# Terra_Spray.net
KiCad netlist of a schematic drawn in Altium Designer
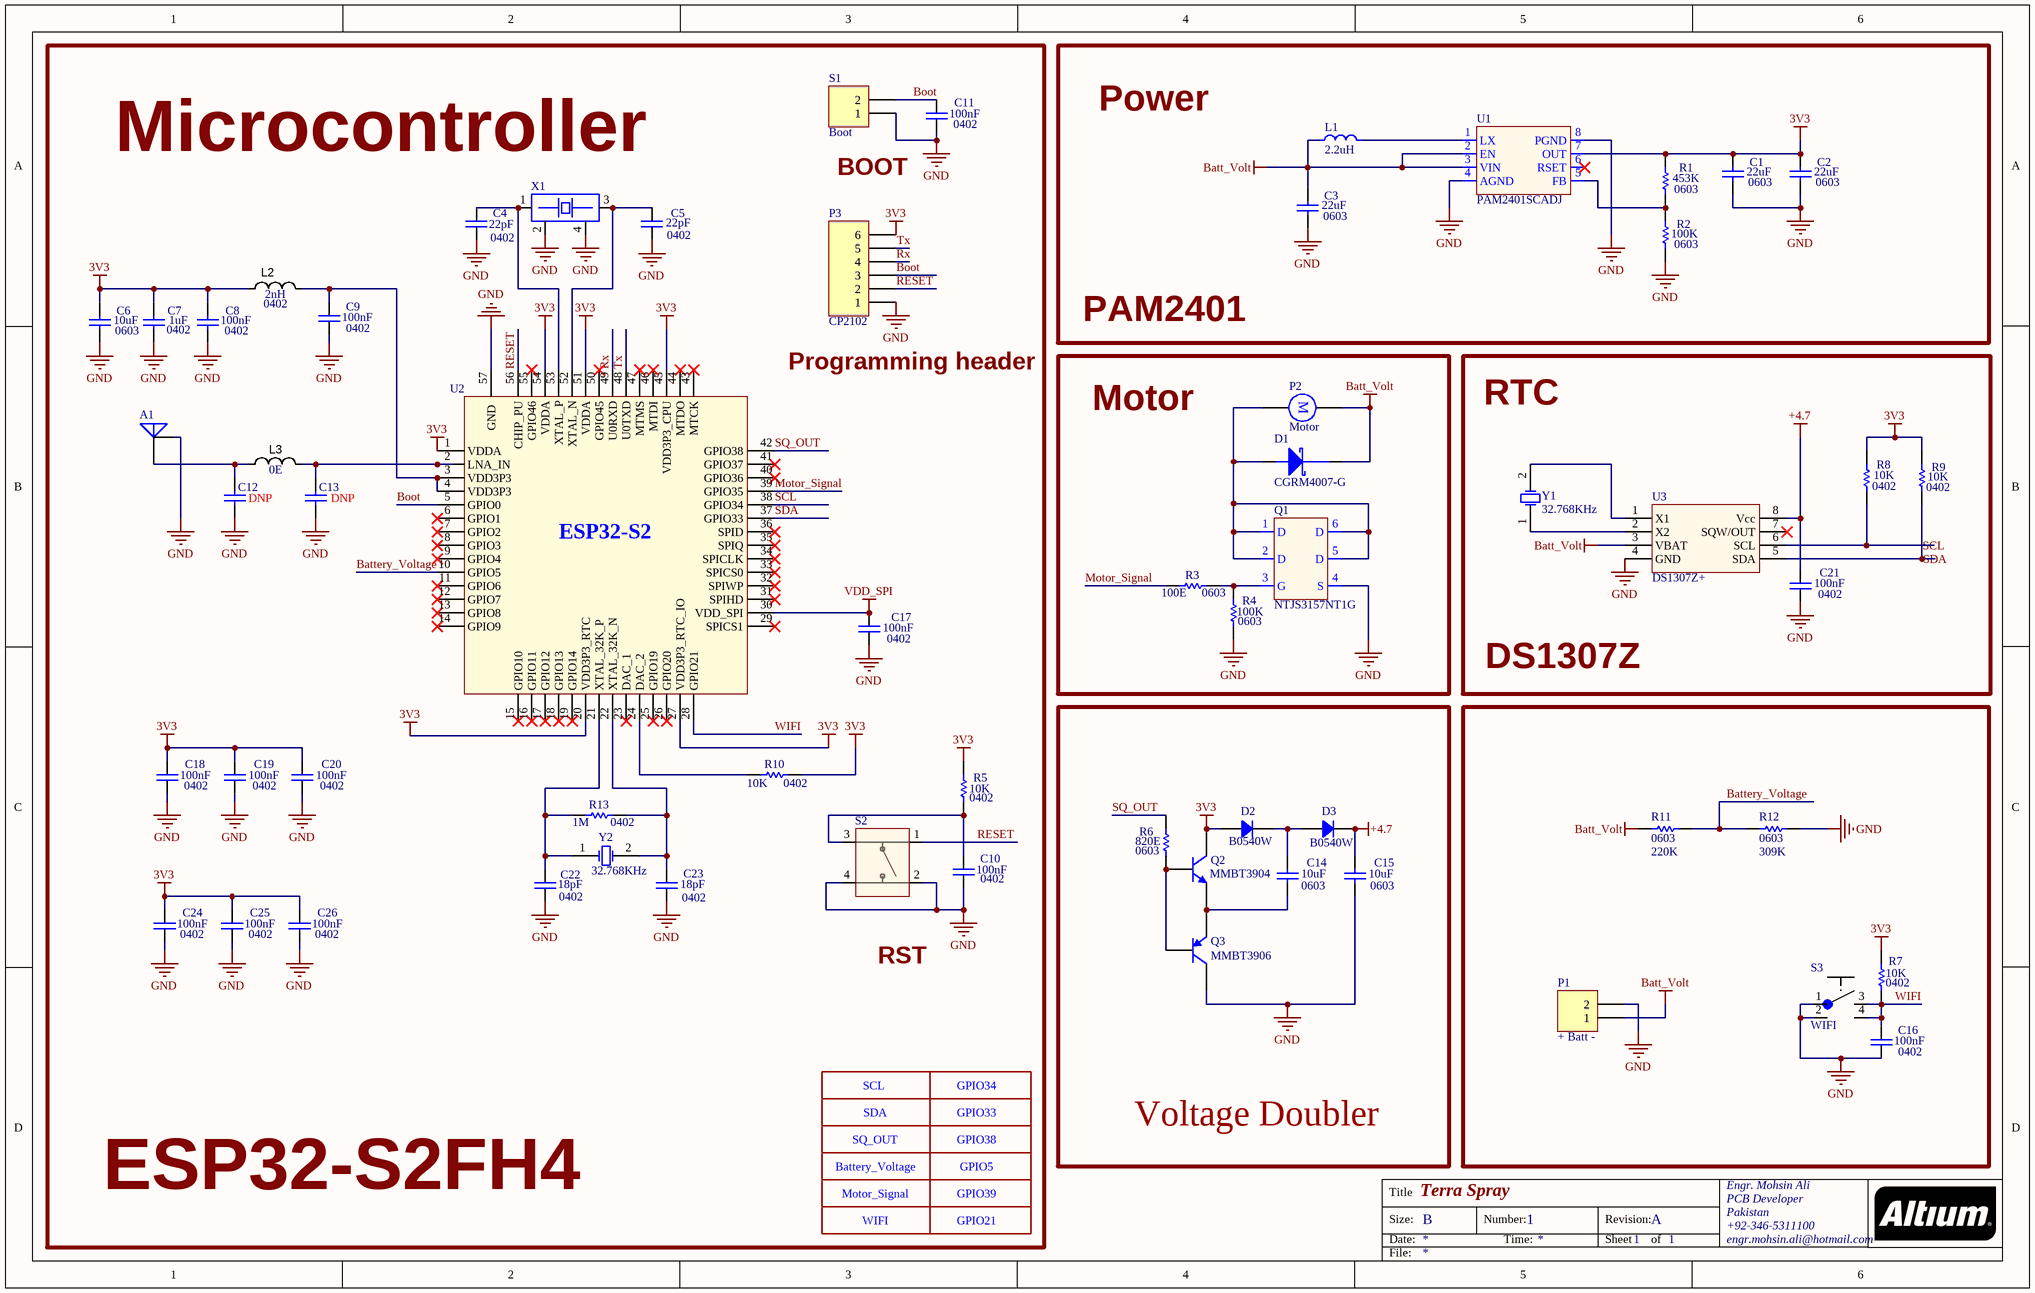
[diagram p0: Terra_Spray.SchDoc]

(export (version "E")
  (design (tool "Eeschema 10.0.6"))
  (components
    (comp (ref "A1")
      (value "Antenna_1")
      (footprint "ESP32 ANT")
      (description "PCB Antenna")
      (fields (field (name "PUBLISHER") "Altium Limited"))
      (libsource (lib "Pd's Sch Lib") (part "Antenna_1"))
    )
    (comp (ref "C1")
      (value "22uF")
      (footprint "CAPC0603")
      (description "Ceramic Capacitor,22uF,0603,6.3V")
      (fields (field (name "CASE/PACKAGE") "0603") (field (name "Comment") "Capacitor"))
      (libsource (lib "Pd's Sch Lib") (part "Capacitor"))
    )
    (comp (ref "C2")
      (value "22uF")
      (footprint "CAPC0603")
      (description "Ceramic Capacitor,22uF,0603,6.3V")
      (fields (field (name "CASE/PACKAGE") "0603") (field (name "Comment") "Capacitor"))
      (libsource (lib "Pd's Sch Lib") (part "Capacitor"))
    )
    (comp (ref "C3")
      (value "22uF")
      (footprint "CAPC0603")
      (description "Ceramic Capacitor,22uF,0603,6.3V")
      (fields (field (name "CASE/PACKAGE") "0603") (field (name "Comment") "Capacitor"))
      (libsource (lib "Pd's Sch Lib") (part "Capacitor"))
    )
    (comp (ref "C4")
      (value "22pF")
      (footprint "capc0402")
      (description "Ceramic Capacitor,22pF,0402,50V")
      (fields (field (name "CASE/PACKAGE") "0402") (field (name "Comment") "Cap"))
      (libsource (lib "CUSTOM TNY290PG") (part "Cap"))
    )
    (comp (ref "C5")
      (value "22pF")
      (footprint "capc0402")
      (description "Ceramic Capacitor,22pF,0402,50V")
      (fields (field (name "CASE/PACKAGE") "0402") (field (name "Comment") "Cap"))
      (libsource (lib "CUSTOM TNY290PG") (part "Cap"))
    )
    (comp (ref "C6")
      (value "10uF")
      (footprint "CAPC0603")
      (description "Ceramic Capacitor,10uF,0603,10V")
      (fields (field (name "CASE/PACKAGE") "0603") (field (name "Comment") "Capacitor"))
      (libsource (lib "Pd's Sch Lib") (part "Capacitor"))
    )
    (comp (ref "C7")
      (value "1uF")
      (footprint "CAPC0402")
      (description "Ceramic Capacitor,1uF,0402,6.3V")
      (fields (field (name "CASE/PACKAGE") "0402") (field (name "Comment") "Capacitor"))
      (libsource (lib "Pd's Sch Lib") (part "Capacitor"))
    )
    (comp (ref "C8")
      (value "100nF")
      (footprint "CAPC0402")
      (description "Ceramic Capacitor,100nF,0402,6.3V")
      (fields (field (name "CASE/PACKAGE") "0402") (field (name "Comment") "Cap"))
      (libsource (lib "Pd's Sch Lib") (part "Capacitor"))
    )
    (comp (ref "C9")
      (value "100nF")
      (footprint "CAPC0402")
      (description "Ceramic Capacitor,100nF,0402,6.3V")
      (fields (field (name "CASE/PACKAGE") "0402") (field (name "Comment") "Cap"))
      (libsource (lib "CUSTOM TNY290PG") (part "Cap"))
    )
    (comp (ref "C10")
      (value "100nF")
      (footprint "CAPC0402")
      (description "Ceramic Capacitor,100nF,0402,6.3V")
      (fields (field (name "CASE/PACKAGE") "0402") (field (name "Comment") "Cap"))
      (libsource (lib "CUSTOM TNY290PG") (part "Cap"))
    )
    (comp (ref "C11")
      (value "100nF")
      (footprint "CAPC0402")
      (description "Ceramic Capacitor,100nF,0402,6.3V")
      (fields (field (name "CASE/PACKAGE") "0402") (field (name "Comment") "Cap"))
      (libsource (lib "CUSTOM TNY290PG") (part "Cap"))
    )
    (comp (ref "C12")
      (value "Capacitor")
      (footprint "CAPC0402")
      (libsource (lib "Pd's Sch Lib") (part "Capacitor"))
    )
    (comp (ref "C13")
      (value "Capacitor")
      (footprint "CAPC0402")
      (libsource (lib "Pd's Sch Lib") (part "Capacitor"))
    )
    (comp (ref "C14")
      (value "10uF")
      (footprint "CAPC0603")
      (description "Ceramic Capacitor,10uF,0603,10V")
      (fields (field (name "CASE/PACKAGE") "0603") (field (name "Comment") "Capacitor"))
      (libsource (lib "") (part "Capacitor_1"))
    )
    (comp (ref "C15")
      (value "10uF")
      (footprint "CAPC0603")
      (description "Ceramic Capacitor,10uF,0603,10V")
      (fields (field (name "CASE/PACKAGE") "0603") (field (name "Comment") "Capacitor"))
      (libsource (lib "") (part "Capacitor_1"))
    )
    (comp (ref "C16")
      (value "100nF")
      (footprint "CAPC0402")
      (description "Ceramic Capacitor,100nF,0402,6.3V")
      (fields (field (name "CASE/PACKAGE") "0402") (field (name "Comment") "Cap"))
      (libsource (lib "CUSTOM TNY290PG") (part "Cap"))
    )
    (comp (ref "C17")
      (value "100nF")
      (footprint "CAPC0402")
      (description "Ceramic Capacitor,100nF,0402,6.3V")
      (fields (field (name "CASE/PACKAGE") "0402") (field (name "Comment") "Cap"))
      (libsource (lib "CUSTOM TNY290PG") (part "Cap"))
    )
    (comp (ref "C18")
      (value "100nF")
      (footprint "CAPC0402")
      (description "Ceramic Capacitor,100nF,0402,6.3V")
      (fields (field (name "CASE/PACKAGE") "0402") (field (name "Comment") "Cap"))
      (libsource (lib "CUSTOM TNY290PG") (part "Cap"))
    )
    (comp (ref "C19")
      (value "100nF")
      (footprint "CAPC0402")
      (description "Ceramic Capacitor,100nF,0402,6.3V")
      (fields (field (name "CASE/PACKAGE") "0402") (field (name "Comment") "Cap"))
      (libsource (lib "CUSTOM TNY290PG") (part "Cap"))
    )
    (comp (ref "C20")
      (value "100nF")
      (footprint "CAPC0402")
      (description "Ceramic Capacitor,100nF,0402,6.3V")
      (fields (field (name "CASE/PACKAGE") "0402") (field (name "Comment") "Cap"))
      (libsource (lib "CUSTOM TNY290PG") (part "Cap"))
    )
    (comp (ref "C21")
      (value "100nF")
      (footprint "CAPC0402")
      (description "Ceramic Capacitor,100nF,0402,6.3V")
      (fields (field (name "CASE/PACKAGE") "0402") (field (name "Comment") "Cap"))
      (libsource (lib "CUSTOM TNY290PG") (part "Cap"))
    )
    (comp (ref "C22")
      (value "18pF")
      (footprint "capc0402")
      (description "Ceramic Capacitor,18pF,0402,50V")
      (fields (field (name "CASE/PACKAGE") "0402") (field (name "Comment") "Cap"))
      (libsource (lib "CUSTOM TNY290PG") (part "Cap"))
    )
    (comp (ref "C23")
      (value "18pF")
      (footprint "capc0402")
      (description "Ceramic Capacitor,18pF,0402,50V")
      (fields (field (name "CASE/PACKAGE") "0402") (field (name "Comment") "Cap"))
      (libsource (lib "CUSTOM TNY290PG") (part "Cap"))
    )
    (comp (ref "C24")
      (value "100nF")
      (footprint "CAPC0402")
      (description "Ceramic Capacitor,100nF,0402,6.3V")
      (fields (field (name "CASE/PACKAGE") "0402") (field (name "Comment") "Cap"))
      (libsource (lib "CUSTOM TNY290PG") (part "Cap"))
    )
    (comp (ref "C25")
      (value "100nF")
      (footprint "CAPC0402")
      (description "Ceramic Capacitor,100nF,0402,6.3V")
      (fields (field (name "CASE/PACKAGE") "0402") (field (name "Comment") "Cap"))
      (libsource (lib "CUSTOM TNY290PG") (part "Cap"))
    )
    (comp (ref "C26")
      (value "100nF")
      (footprint "CAPC0402")
      (description "Ceramic Capacitor,100nF,0402,6.3V")
      (fields (field (name "CASE/PACKAGE") "0402") (field (name "Comment") "Cap"))
      (libsource (lib "CUSTOM TNY290PG") (part "Cap"))
    )
    (comp (ref "D1")
      (value "CGRM4007-G")
      (footprint "SOD-123")
      (description "CGRM4007-G; SMT Diode; 1000V 1A; 2-Pin SOD-123")
      (fields (field (name "MANUFACTURER") "Comchip") (field (name "VOLTAGE") "1kV"))
      (libsource (lib "Integrated_Library_FEDEVEL_APR_2015") (part "BAT54HT1G"))
    )
    (comp (ref "D2")
      (value "B0540W")
      (footprint "SOD123 - duplicate")
      (description "Diode Schottky 40V 0.5A 2-Pin SOD-123 T/R")
      (libsource (lib "Pd's Sch Lib") (part "Diode"))
    )
    (comp (ref "D3")
      (value "B0540W")
      (footprint "SOD123 - duplicate")
      (description "Diode Schottky 40V 0.5A 2-Pin SOD-123 T/R")
      (libsource (lib "Pd's Sch Lib") (part "Diode"))
    )
    (comp (ref "L1")
      (value "2.2uH")
      (footprint "INDP5050X20N")
      (description "SMD Power Inductors ROHS")
      (fields (field (name "MANUFACTURER PART NUMBER") "FNR5012S2R2MT") (field (name "Comment") "Inductor"))
      (libsource (lib "Inductors") (part "74404052022"))
    )
    (comp (ref "L2")
      (value "Inductor")
      (footprint "inductor 0402")
      (description "2nH ±0.3nH 900mA 120mΩ 0402 Inductors (SMD) RoHS")
      (fields
        (field (name "MANUFACTURER PART NUMBER") "LQG15HN2N0S02D")
        (field (name "CASE/PACKAGE") "0402")
        (field (name "INDUCTANCE") "2nH")
      )
      (libsource (lib "Pd's Sch Lib") (part "Inductor"))
    )
    (comp (ref "L3")
      (value "0E")
      (footprint "inductor 0402")
      (description "Thick Film Resistor -  0ohm, 1%, 0402")
      (fields (field (name "Comment") "Inductor"))
      (libsource (lib "Pd's Sch Lib") (part "Inductor"))
    )
    (comp (ref "P1")
      (value "+ Batt -")
      (footprint "2 pin 2.5mm - Header")
      (description "Header, 2-Pin")
      (fields (field (name "PUBLISHER") "Altium Limited"))
      (libsource (lib "Miscellaneous Connectors") (part "Header 2"))
    )
    (comp (ref "P2")
      (value "Motor")
      (footprint "2 pin 2.5mm - Header")
      (description "Motor, General Kind")
      (fields (field (name "PUBLISHER") "Altium Limited"))
      (libsource (lib "Miscellaneous Devices") (part "Motor"))
    )
    (comp (ref "P3")
      (value "CP2102")
      (footprint "Header 6x1")
      (description "Header, 6-Pin")
      (fields (field (name "PUBLISHER") "Altium Limited"))
      (libsource (lib "Miscellaneous Connectors") (part "Header 6"))
    )
    (comp (ref "Q1")
      (value "Mosfet")
      (footprint "SOT-363")
      (description "Trans MOSFET N-CH 20V 3.2A 6-Pin SC-88 T/R")
      (fields (field (name "MANUFACTURER PART NUMBER") "NTJS3157NT1G"))
      (libsource (lib "Terra_Spray") (part "NTJS3157NT1G"))
    )
    (comp (ref "Q2")
      (value "NPN BJT Transistor")
      (footprint "SOT-23")
      (description "Bipolar Transistors - BJT SOT-23 NPN")
      (fields (field (name "MANUFACTURER PART NUMBER") "MMBT3904"))
      (libsource (lib "Pd's Sch Lib") (part "NPN BJT Transistor"))
    )
    (comp (ref "Q3")
      (value "PNP BJT Transistor")
      (footprint "SOT-23")
      (fields
        (field (name "MANUFACTURER") "ON Semiconductor")
        (field (name "MANUFACTURER PART NUMBER") "MMBT3906")
      )
      (libsource (lib "Pd's Sch Lib") (part "PNP BJT Transistor"))
    )
    (comp (ref "R1")
      (value "453K")
      (footprint "RESC0603")
      (description "Thick Film Resistor -  453Kohm, 1%, 0603")
      (fields (field (name "CASE/PACKAGE") "0603") (field (name "Comment") "Resistor"))
      (libsource (lib "Pd's Sch Lib") (part "Resistor"))
    )
    (comp (ref "R2")
      (value "100K")
      (footprint "RESC0603")
      (description "Thick Film Resistor -  100Kohm, 1%, 0603")
      (fields (field (name "CASE/PACKAGE") "0603") (field (name "Comment") "Resistor"))
      (libsource (lib "Pd's Sch Lib") (part "Resistor"))
    )
    (comp (ref "R3")
      (value "100E")
      (footprint "RESC0603")
      (description "Thick Film Resistor -  100ohm, 1%, 0603")
      (fields (field (name "CASE/PACKAGE") "0603") (field (name "Comment") "Resistor"))
      (libsource (lib "Pd's Sch Lib") (part "Resistor"))
    )
    (comp (ref "R4")
      (value "100K")
      (footprint "RESC0603")
      (description "Thick Film Resistor -  100Kohm, 1%, 0603")
      (fields (field (name "CASE/PACKAGE") "0603") (field (name "Comment") "Resistor"))
      (libsource (lib "Pd's Sch Lib") (part "Resistor"))
    )
    (comp (ref "R5")
      (value "10K")
      (footprint "RESC0402")
      (description "Thick Film Resistor -  10Kohm, 1%, 0402")
      (fields (field (name "CASE/PACKAGE") "0402") (field (name "Comment") "Resistor"))
      (libsource (lib "Pd's Sch Lib") (part "Resistor"))
    )
    (comp (ref "R6")
      (value "820E")
      (footprint "RESC0603")
      (description "Thick Film Resistor -  820ohm, 1%, 0603")
      (fields (field (name "CASE/PACKAGE") "0603") (field (name "Comment") "Resistor"))
      (libsource (lib "Pd's Sch Lib") (part "Resistor"))
    )
    (comp (ref "R7")
      (value "10K")
      (footprint "RESC0402")
      (description "Thick Film Resistor -  10Kohm, 1%, 0402")
      (fields (field (name "CASE/PACKAGE") "0402") (field (name "Comment") "Resistor"))
      (libsource (lib "Pd's Sch Lib") (part "Resistor"))
    )
    (comp (ref "R8")
      (value "10K")
      (footprint "RESC0402")
      (description "Thick Film Resistor -  10Kohm, 1%, 0402")
      (fields (field (name "CASE/PACKAGE") "0402") (field (name "Comment") "Resistor"))
      (libsource (lib "Pd's Sch Lib") (part "Resistor"))
    )
    (comp (ref "R9")
      (value "10K")
      (footprint "RESC0402")
      (description "Thick Film Resistor -  10Kohm, 1%, 0402")
      (fields (field (name "CASE/PACKAGE") "0402") (field (name "Comment") "Resistor"))
      (libsource (lib "Pd's Sch Lib") (part "Resistor"))
    )
    (comp (ref "R10")
      (value "10K")
      (footprint "RESC0402")
      (description "Thick Film Resistor -  10Kohm, 1%, 0402")
      (fields (field (name "CASE/PACKAGE") "0402") (field (name "Comment") "Resistor"))
      (libsource (lib "Pd's Sch Lib") (part "Resistor"))
    )
    (comp (ref "R11")
      (value "220K")
      (footprint "RESC0603")
      (description "Thick Film Resistor -  220Kohm, 1%, 0603")
      (fields (field (name "CASE/PACKAGE") "0603") (field (name "Comment") "Resistor"))
      (libsource (lib "Pd's Sch Lib") (part "Resistor"))
    )
    (comp (ref "R12")
      (value "309K")
      (footprint "RESC0603")
      (description "Thick Film Resistor -  309Kohm, 1%, 0603")
      (fields (field (name "CASE/PACKAGE") "0603") (field (name "Comment") "Resistor"))
      (libsource (lib "Pd's Sch Lib") (part "Resistor"))
    )
    (comp (ref "R13")
      (value "1M")
      (footprint "RESC0402")
      (description "Thick Film Resistor -  1Mohm, 1%, 0402")
      (fields (field (name "CASE/PACKAGE") "0402") (field (name "Comment") "Resistor"))
      (libsource (lib "Pd's Sch Lib") (part "Resistor"))
    )
    (comp (ref "S1")
      (value "Boot")
      (footprint "Switch Replacement")
      (description "Header, 2-Pin")
      (fields (field (name "PUBLISHER") "Altium Limited"))
      (libsource (lib "Miscellaneous Connectors") (part "Header 2"))
    )
    (comp (ref "S2")
      (value "Button")
      (footprint "434153017835")
      (description "3mm Square Plunger 50mA Top触动 3.5mm SPST 12V SMD Tactile Switches ROHS")
      (fields (field (name "MANUFACTURER PART NUMBER") "TS-1809SM-C"))
      (libsource (lib "Buttons") (part "434153017835"))
    )
    (comp (ref "S3")
      (value "WIFI")
      (footprint "FSMJ - SMD - Wifi")
      (description "Pushbutton 6x6mm, Actuator Height off PCB, Vertical 9.50mm")
      (fields (field (name "MF") "TE Connectivity") (field (name "MP") "FSM14J"))
      (libsource (lib "Main_PCB") (part "FSM14J"))
    )
    (comp (ref "U1")
      (value "PAM2401SCADJ")
      (footprint "8-TSSOP, 8-MSOP")
      (description "IC REG BOOST ADJ 3A SYNC 8MSOP")
      (libsource (lib "Regulators") (part "PAM2401SCADJ"))
    )
    (comp (ref "U2")
      (value "ESP32-S2")
      (footprint "QFN56-7x7mm")
      (description "WiFi 802.11b/g/n Transceiver Module 2.4GHz")
      (fields (field (name "MANUFACTURER PART NUMBER") "ESP32-S2FH4"))
      (libsource (lib "Pd's Sch Lib") (part "ESP32-S2"))
    )
    (comp (ref "U3")
      (value "DS1307Z+")
      (footprint "SOIC-8")
      (description "SERIAL TIME CHIP 8PIN, SOIC")
      (fields (field (name "VOLTAGE") "5V"))
      (libsource (lib "IC's") (part "DS1307Z+"))
    )
    (comp (ref "X1")
      (value "CRYSTAL_1")
      (footprint "Crystal_3225")
      (description "40MHz ±10ppm 10pF 30Ω SMD-3225 SMD Crystal Resonators RoHS")
      (fields (field (name "MANUFACTURER PART NUMBER") "7M40000049"))
      (libsource (lib "Pd's Sch Lib") (part "CRYSTAL_1_1"))
    )
    (comp (ref "Y1")
      (value "32.768KHz")
      (footprint "32.728Khz")
      (description "Crystal Oscillator")
      (fields (field (name "PUBLISHER") "Altium Limited"))
      (libsource (lib "Miscellaneous Devices") (part "XTAL"))
    )
    (comp (ref "Y2")
      (value "32.768KHz")
      (footprint "32.728Khz")
      (description "Crystal Oscillator")
      (fields (field (name "PUBLISHER") "Altium Limited"))
      (libsource (lib "Miscellaneous Devices") (part "XTAL"))
    )
  )
  (nets
    (net (code "1") (name "+4.7") (class "Default")
      (node (ref "C15") (pin "1") (pinfunction "1_1") (pintype "passive"))
      (node (ref "C21") (pin "1") (pinfunction "1_1") (pintype "passive"))
      (node (ref "D3") (pin "K") (pinfunction "K_K") (pintype "passive"))
      (node (ref "U3") (pin "8") (pinfunction "Vcc_8") (pintype "passive"))
    )
    (net (code "2") (name "/Battery_Voltage") (class "Default")
      (node (ref "R11") (pin "1") (pinfunction "1_1") (pintype "passive"))
      (node (ref "R12") (pin "2") (pinfunction "2_2") (pintype "passive"))
      (node (ref "U2") (pin "10") (pinfunction "GPIO5_10") (pintype "passive"))
    )
    (net (code "3") (name "/Boot") (class "Default")
      (node (ref "C11") (pin "2") (pinfunction "2_2") (pintype "passive"))
      (node (ref "P3") (pin "3") (pinfunction "3_3") (pintype "passive"))
      (node (ref "S1") (pin "2") (pinfunction "2_2") (pintype "passive"))
      (node (ref "U2") (pin "5") (pinfunction "GPIO0_5") (pintype "passive"))
    )
    (net (code "10") (name "/Motor_Signal") (class "Default")
      (node (ref "R3") (pin "2") (pinfunction "2_2") (pintype "passive"))
      (node (ref "U2") (pin "39") (pinfunction "GPIO35_39") (pintype "passive"))
    )
    (net (code "11") (name "/RESET") (class "Default")
      (node (ref "P3") (pin "2") (pinfunction "2_2") (pintype "passive"))
      (node (ref "S2") (pin "1") (pinfunction "1_1") (pintype "passive"))
      (node (ref "U2") (pin "56") (pinfunction "CHIP_PU_56") (pintype "passive"))
    )
    (net (code "12") (name "/Rx") (class "Default")
      (node (ref "P3") (pin "4") (pinfunction "4_4") (pintype "passive"))
      (node (ref "U2") (pin "49") (pinfunction "U0RXD_49") (pintype "passive"))
    )
    (net (code "13") (name "/SCL") (class "Default")
      (node (ref "R8") (pin "1") (pinfunction "1_1") (pintype "passive"))
      (node (ref "U2") (pin "38") (pinfunction "GPIO34_38") (pintype "passive"))
      (node (ref "U3") (pin "6") (pinfunction "SCL_6") (pintype "passive"))
    )
    (net (code "14") (name "/SDA") (class "Default")
      (node (ref "R9") (pin "1") (pinfunction "1_1") (pintype "passive"))
      (node (ref "U2") (pin "37") (pinfunction "GPIO33_37") (pintype "passive"))
      (node (ref "U3") (pin "5") (pinfunction "SDA_5") (pintype "passive"))
    )
    (net (code "15") (name "/SQ_OUT") (class "Default")
      (node (ref "R6") (pin "2") (pinfunction "2_2") (pintype "passive"))
      (node (ref "U2") (pin "42") (pinfunction "GPIO38_42") (pintype "passive"))
    )
    (net (code "16") (name "/Tx") (class "Default")
      (node (ref "P3") (pin "5") (pinfunction "5_5") (pintype "passive"))
      (node (ref "U2") (pin "48") (pinfunction "U0TXD_48") (pintype "passive"))
    )
    (net (code "17") (name "/WIFI") (class "Default")
      (node (ref "C16") (pin "2") (pinfunction "2_2") (pintype "passive"))
      (node (ref "R7") (pin "1") (pinfunction "1_1") (pintype "passive"))
      (node (ref "S3") (pin "3") (pinfunction "2_3") (pintype "passive"))
      (node (ref "S3") (pin "4") (pinfunction "2_4") (pintype "passive"))
      (node (ref "U2") (pin "28") (pinfunction "GPIO21_28") (pintype "passive"))
    )
    (net (code "18") (name "3V3") (class "Default")
      (node (ref "C1") (pin "2") (pinfunction "2_2") (pintype "passive"))
      (node (ref "C18") (pin "1") (pinfunction "1_1") (pintype "passive"))
      (node (ref "C19") (pin "1") (pinfunction "1_1") (pintype "passive"))
      (node (ref "C2") (pin "2") (pinfunction "2_2") (pintype "passive"))
      (node (ref "C20") (pin "1") (pinfunction "1_1") (pintype "passive"))
      (node (ref "C24") (pin "1") (pinfunction "1_1") (pintype "passive"))
      (node (ref "C25") (pin "1") (pinfunction "1_1") (pintype "passive"))
      (node (ref "C26") (pin "1") (pinfunction "1_1") (pintype "passive"))
      (node (ref "C6") (pin "2") (pinfunction "2_2") (pintype "passive"))
      (node (ref "C7") (pin "2") (pinfunction "2_2") (pintype "passive"))
      (node (ref "C8") (pin "2") (pinfunction "2_2") (pintype "passive"))
      (node (ref "D2") (pin "A") (pinfunction "A_A") (pintype "passive"))
      (node (ref "L2") (pin "1") (pinfunction "1_1") (pintype "passive"))
      (node (ref "P3") (pin "6") (pinfunction "6_6") (pintype "passive"))
      (node (ref "Q2") (pin "3") (pinfunction "C_3") (pintype "passive"))
      (node (ref "R1") (pin "2") (pinfunction "2_2") (pintype "passive"))
      (node (ref "R10") (pin "1") (pinfunction "1_1") (pintype "passive"))
      (node (ref "R5") (pin "2") (pinfunction "2_2") (pintype "passive"))
      (node (ref "R7") (pin "2") (pinfunction "2_2") (pintype "passive"))
      (node (ref "R8") (pin "2") (pinfunction "2_2") (pintype "passive"))
      (node (ref "R9") (pin "2") (pinfunction "2_2") (pintype "passive"))
      (node (ref "U1") (pin "7") (pinfunction "OUT_7") (pintype "passive"))
      (node (ref "U2") (pin "1") (pinfunction "VDDA_1") (pintype "passive"))
      (node (ref "U2") (pin "20") (pinfunction "VDD3P3_RTC_20") (pintype "passive"))
      (node (ref "U2") (pin "27") (pinfunction "VDD3P3_RTC_IO_27") (pintype "passive"))
      (node (ref "U2") (pin "45") (pinfunction "VDD3P3_CPU_45") (pintype "passive"))
      (node (ref "U2") (pin "51") (pinfunction "VDDA_51") (pintype "passive"))
      (node (ref "U2") (pin "54") (pinfunction "VDDA_54") (pintype "passive"))
    )
    (net (code "19") (name "Batt_Volt") (class "Default")
      (node (ref "C3") (pin "2") (pinfunction "2_2") (pintype "passive"))
      (node (ref "D1") (pin "1") (pinfunction "Cathode_1") (pintype "passive"))
      (node (ref "L1") (pin "1") (pinfunction "1_1") (pintype "passive"))
      (node (ref "P1") (pin "1") (pinfunction "1_1") (pintype "passive"))
      (node (ref "P2") (pin "1") (pinfunction "1_1") (pintype "passive"))
      (node (ref "R11") (pin "2") (pinfunction "2_2") (pintype "passive"))
      (node (ref "U1") (pin "2") (pinfunction "EN_2") (pintype "passive"))
      (node (ref "U1") (pin "3") (pinfunction "VIN_3") (pintype "passive"))
      (node (ref "U3") (pin "3") (pinfunction "VBAT_3") (pintype "passive"))
    )
    (net (code "20") (name "GND") (class "Default")
      (node (ref "A1") (pin "2") (pinfunction "GND_2") (pintype "passive"))
      (node (ref "C1") (pin "1") (pinfunction "1_1") (pintype "passive"))
      (node (ref "C10") (pin "2") (pinfunction "2_2") (pintype "passive"))
      (node (ref "C11") (pin "1") (pinfunction "1_1") (pintype "passive"))
      (node (ref "C12") (pin "1") (pinfunction "1_1") (pintype "passive"))
      (node (ref "C13") (pin "1") (pinfunction "1_1") (pintype "passive"))
      (node (ref "C15") (pin "2") (pinfunction "2_2") (pintype "passive"))
      (node (ref "C16") (pin "1") (pinfunction "1_1") (pintype "passive"))
      (node (ref "C17") (pin "2") (pinfunction "2_2") (pintype "passive"))
      (node (ref "C18") (pin "2") (pinfunction "2_2") (pintype "passive"))
      (node (ref "C19") (pin "2") (pinfunction "2_2") (pintype "passive"))
      (node (ref "C2") (pin "1") (pinfunction "1_1") (pintype "passive"))
      (node (ref "C20") (pin "2") (pinfunction "2_2") (pintype "passive"))
      (node (ref "C21") (pin "2") (pinfunction "2_2") (pintype "passive"))
      (node (ref "C22") (pin "1") (pinfunction "1_1") (pintype "passive"))
      (node (ref "C23") (pin "1") (pinfunction "1_1") (pintype "passive"))
      (node (ref "C24") (pin "2") (pinfunction "2_2") (pintype "passive"))
      (node (ref "C25") (pin "2") (pinfunction "2_2") (pintype "passive"))
      (node (ref "C26") (pin "2") (pinfunction "2_2") (pintype "passive"))
      (node (ref "C3") (pin "1") (pinfunction "1_1") (pintype "passive"))
      (node (ref "C4") (pin "1") (pinfunction "1_1") (pintype "passive"))
      (node (ref "C5") (pin "1") (pinfunction "1_1") (pintype "passive"))
      (node (ref "C6") (pin "1") (pinfunction "1_1") (pintype "passive"))
      (node (ref "C7") (pin "1") (pinfunction "1_1") (pintype "passive"))
      (node (ref "C8") (pin "1") (pinfunction "1_1") (pintype "passive"))
      (node (ref "C9") (pin "2") (pinfunction "2_2") (pintype "passive"))
      (node (ref "P1") (pin "2") (pinfunction "2_2") (pintype "passive"))
      (node (ref "P3") (pin "1") (pinfunction "1_1") (pintype "passive"))
      (node (ref "Q1") (pin "4") (pinfunction "S_4") (pintype "passive"))
      (node (ref "Q3") (pin "3") (pinfunction "C_3") (pintype "passive"))
      (node (ref "R12") (pin "1") (pinfunction "1_1") (pintype "passive"))
      (node (ref "R2") (pin "2") (pinfunction "2_2") (pintype "passive"))
      (node (ref "R4") (pin "2") (pinfunction "2_2") (pintype "passive"))
      (node (ref "S1") (pin "1") (pinfunction "1_1") (pintype "passive"))
      (node (ref "S2") (pin "2") (pinfunction "2_2") (pintype "passive"))
      (node (ref "S2") (pin "4") (pinfunction "4_4") (pintype "passive"))
      (node (ref "S3") (pin "1") (pinfunction "1_1") (pintype "passive"))
      (node (ref "S3") (pin "2") (pinfunction "1_2") (pintype "passive"))
      (node (ref "U1") (pin "4") (pinfunction "AGND_4") (pintype "passive"))
      (node (ref "U1") (pin "8") (pinfunction "PGND_8") (pintype "passive"))
      (node (ref "U2") (pin "57") (pinfunction "GND_57") (pintype "passive"))
      (node (ref "U3") (pin "4") (pinfunction "GND_4") (pintype "passive"))
      (node (ref "X1") (pin "2") (pinfunction "2_2") (pintype "passive"))
      (node (ref "X1") (pin "4") (pinfunction "4_4") (pintype "passive"))
    )
    (net (code "21") (name "Net-(A1-ANT)") (class "Default")
      (node (ref "A1") (pin "1") (pinfunction "ANT_1") (pintype "passive"))
      (node (ref "C12") (pin "2") (pinfunction "2_2") (pintype "passive"))
      (node (ref "L3") (pin "1") (pinfunction "1_1") (pintype "passive"))
    )
    (net (code "22") (name "Net-(C9-Pad1)") (class "Default")
      (node (ref "C9") (pin "1") (pinfunction "1_1") (pintype "passive"))
      (node (ref "L2") (pin "2") (pinfunction "2_2") (pintype "passive"))
      (node (ref "U2") (pin "3") (pinfunction "VDD3P3_3") (pintype "passive"))
      (node (ref "U2") (pin "4") (pinfunction "VDD3P3_4") (pintype "passive"))
    )
    (net (code "23") (name "Net-(C10-Pad1)") (class "Default")
      (node (ref "C10") (pin "1") (pinfunction "1_1") (pintype "passive"))
      (node (ref "R5") (pin "1") (pinfunction "1_1") (pintype "passive"))
      (node (ref "S2") (pin "3") (pinfunction "3_3") (pintype "passive"))
    )
    (net (code "24") (name "Net-(C14-Pad1)") (class "Default")
      (node (ref "C14") (pin "1") (pinfunction "1_1") (pintype "passive"))
      (node (ref "D2") (pin "K") (pinfunction "K_K") (pintype "passive"))
      (node (ref "D3") (pin "A") (pinfunction "A_A") (pintype "passive"))
    )
    (net (code "25") (name "Net-(D1-Anode)") (class "Default")
      (node (ref "D1") (pin "2") (pinfunction "Anode_2") (pintype "passive"))
      (node (ref "P2") (pin "2") (pinfunction "2_2") (pintype "passive"))
      (node (ref "Q1") (pin "1") (pinfunction "D_1") (pintype "passive"))
      (node (ref "Q1") (pin "2") (pinfunction "D_2") (pintype "passive"))
      (node (ref "Q1") (pin "5") (pinfunction "D_5") (pintype "passive"))
      (node (ref "Q1") (pin "6") (pinfunction "D_6") (pintype "passive"))
    )
    (net (code "26") (name "Net-(Q1-G)") (class "Default")
      (node (ref "Q1") (pin "3") (pinfunction "G_3") (pintype "passive"))
      (node (ref "R3") (pin "1") (pinfunction "1_1") (pintype "passive"))
      (node (ref "R4") (pin "1") (pinfunction "1_1") (pintype "passive"))
    )
    (net (code "27") (name "Net-(Q2-B)") (class "Default")
      (node (ref "Q2") (pin "1") (pinfunction "B_1") (pintype "passive"))
      (node (ref "Q3") (pin "1") (pinfunction "B_1") (pintype "passive"))
      (node (ref "R6") (pin "1") (pinfunction "1_1") (pintype "passive"))
    )
    (net (code "28") (name "Net-(Q2-E)") (class "Default")
      (node (ref "C14") (pin "2") (pinfunction "2_2") (pintype "passive"))
      (node (ref "Q2") (pin "2") (pinfunction "E_2") (pintype "passive"))
      (node (ref "Q3") (pin "2") (pinfunction "E_2") (pintype "passive"))
    )
    (net (code "29") (name "Net-(U1-FB)") (class "Default")
      (node (ref "R1") (pin "1") (pinfunction "1_1") (pintype "passive"))
      (node (ref "R2") (pin "1") (pinfunction "1_1") (pintype "passive"))
      (node (ref "U1") (pin "5") (pinfunction "FB_5") (pintype "passive"))
    )
    (net (code "30") (name "Net-(U1-LX)") (class "Default")
      (node (ref "L1") (pin "2") (pinfunction "2_2") (pintype "passive"))
      (node (ref "U1") (pin "1") (pinfunction "LX_1") (pintype "passive"))
    )
    (net (code "31") (name "Net-(U2-DAC_2)") (class "Default")
      (node (ref "R10") (pin "2") (pinfunction "2_2") (pintype "passive"))
      (node (ref "U2") (pin "24") (pinfunction "DAC_2_24") (pintype "passive"))
    )
    (net (code "32") (name "Net-(U2-LNA_IN)") (class "Default")
      (node (ref "C13") (pin "2") (pinfunction "2_2") (pintype "passive"))
      (node (ref "L3") (pin "2") (pinfunction "2_2") (pintype "passive"))
      (node (ref "U2") (pin "2") (pinfunction "LNA_IN_2") (pintype "passive"))
    )
    (net (code "33") (name "Net-(U2-XTAL_32K_N)") (class "Default")
      (node (ref "C23") (pin "2") (pinfunction "2_2") (pintype "passive"))
      (node (ref "R13") (pin "2") (pinfunction "2_2") (pintype "passive"))
      (node (ref "U2") (pin "22") (pinfunction "XTAL_32K_N_22") (pintype "passive"))
      (node (ref "Y2") (pin "2") (pinfunction "OSC2_2") (pintype "passive"))
    )
    (net (code "34") (name "Net-(U2-XTAL_32K_P)") (class "Default")
      (node (ref "C22") (pin "2") (pinfunction "2_2") (pintype "passive"))
      (node (ref "R13") (pin "1") (pinfunction "1_1") (pintype "passive"))
      (node (ref "U2") (pin "21") (pinfunction "XTAL_32K_P_21") (pintype "passive"))
      (node (ref "Y2") (pin "1") (pinfunction "OSC1_1") (pintype "passive"))
    )
    (net (code "35") (name "Net-(U2-XTAL_N)") (class "Default")
      (node (ref "C5") (pin "2") (pinfunction "2_2") (pintype "passive"))
      (node (ref "U2") (pin "52") (pinfunction "XTAL_N_52") (pintype "passive"))
      (node (ref "X1") (pin "3") (pinfunction "3_3") (pintype "passive"))
    )
    (net (code "36") (name "Net-(U2-XTAL_P)") (class "Default")
      (node (ref "C4") (pin "2") (pinfunction "2_2") (pintype "passive"))
      (node (ref "U2") (pin "53") (pinfunction "XTAL_P_53") (pintype "passive"))
      (node (ref "X1") (pin "1") (pinfunction "1_1") (pintype "passive"))
    )
    (net (code "37") (name "Net-(U3-X1)") (class "Default")
      (node (ref "U3") (pin "1") (pinfunction "X1_1") (pintype "passive"))
      (node (ref "Y1") (pin "2") (pinfunction "OSC2_2") (pintype "passive"))
    )
    (net (code "38") (name "Net-(U3-X2)") (class "Default")
      (node (ref "U3") (pin "2") (pinfunction "X2_2") (pintype "passive"))
      (node (ref "Y1") (pin "1") (pinfunction "OSC1_1") (pintype "passive"))
    )
    (net (code "39") (name "VDD_SPI") (class "Default")
      (node (ref "C17") (pin "1") (pinfunction "1_1") (pintype "passive"))
      (node (ref "U2") (pin "30") (pinfunction "VDD_SPI_30") (pintype "passive"))
    )
    (net (code "40") (name "unconnected-(U1-RSET-Pad6)") (class "Default")
      (node (ref "U1") (pin "6") (pinfunction "RSET_6") (pintype "passive+no_connect"))
    )
    (net (code "41") (name "unconnected-(U2-DAC_1-Pad23)") (class "Default")
      (node (ref "U2") (pin "23") (pinfunction "DAC_1_23") (pintype "passive+no_connect"))
    )
    (net (code "42") (name "unconnected-(U2-GPIO1-Pad6)") (class "Default")
      (node (ref "U2") (pin "6") (pinfunction "GPIO1_6") (pintype "passive+no_connect"))
    )
    (net (code "43") (name "unconnected-(U2-GPIO2-Pad7)") (class "Default")
      (node (ref "U2") (pin "7") (pinfunction "GPIO2_7") (pintype "passive+no_connect"))
    )
    (net (code "44") (name "unconnected-(U2-GPIO3-Pad8)") (class "Default")
      (node (ref "U2") (pin "8") (pinfunction "GPIO3_8") (pintype "passive+no_connect"))
    )
    (net (code "45") (name "unconnected-(U2-GPIO4-Pad9)") (class "Default")
      (node (ref "U2") (pin "9") (pinfunction "GPIO4_9") (pintype "passive+no_connect"))
    )
    (net (code "46") (name "unconnected-(U2-GPIO6-Pad11)") (class "Default")
      (node (ref "U2") (pin "11") (pinfunction "GPIO6_11") (pintype "passive+no_connect"))
    )
    (net (code "47") (name "unconnected-(U2-GPIO7-Pad12)") (class "Default")
      (node (ref "U2") (pin "12") (pinfunction "GPIO7_12") (pintype "passive+no_connect"))
    )
    (net (code "48") (name "unconnected-(U2-GPIO8-Pad13)") (class "Default")
      (node (ref "U2") (pin "13") (pinfunction "GPIO8_13") (pintype "passive+no_connect"))
    )
    (net (code "49") (name "unconnected-(U2-GPIO9-Pad14)") (class "Default")
      (node (ref "U2") (pin "14") (pinfunction "GPIO9_14") (pintype "passive+no_connect"))
    )
    (net (code "50") (name "unconnected-(U2-GPIO10-Pad15)") (class "Default")
      (node (ref "U2") (pin "15") (pinfunction "GPIO10_15") (pintype "passive+no_connect"))
    )
    (net (code "51") (name "unconnected-(U2-GPIO11-Pad16)") (class "Default")
      (node (ref "U2") (pin "16") (pinfunction "GPIO11_16") (pintype "passive+no_connect"))
    )
    (net (code "52") (name "unconnected-(U2-GPIO12-Pad17)") (class "Default")
      (node (ref "U2") (pin "17") (pinfunction "GPIO12_17") (pintype "passive+no_connect"))
    )
    (net (code "53") (name "unconnected-(U2-GPIO13-Pad18)") (class "Default")
      (node (ref "U2") (pin "18") (pinfunction "GPIO13_18") (pintype "passive+no_connect"))
    )
    (net (code "54") (name "unconnected-(U2-GPIO14-Pad19)") (class "Default")
      (node (ref "U2") (pin "19") (pinfunction "GPIO14_19") (pintype "passive+no_connect"))
    )
    (net (code "55") (name "unconnected-(U2-GPIO19-Pad25)") (class "Default")
      (node (ref "U2") (pin "25") (pinfunction "GPIO19_25") (pintype "passive+no_connect"))
    )
    (net (code "56") (name "unconnected-(U2-GPIO20-Pad26)") (class "Default")
      (node (ref "U2") (pin "26") (pinfunction "GPIO20_26") (pintype "passive+no_connect"))
    )
    (net (code "57") (name "unconnected-(U2-GPIO36-Pad40)") (class "Default")
      (node (ref "U2") (pin "40") (pinfunction "GPIO36_40") (pintype "passive+no_connect"))
    )
    (net (code "58") (name "unconnected-(U2-GPIO37-Pad41)") (class "Default")
      (node (ref "U2") (pin "41") (pinfunction "GPIO37_41") (pintype "passive+no_connect"))
    )
    (net (code "59") (name "unconnected-(U2-GPIO45-Pad50)") (class "Default")
      (node (ref "U2") (pin "50") (pinfunction "GPIO45_50") (pintype "passive+no_connect"))
    )
    (net (code "60") (name "unconnected-(U2-GPIO46-Pad55)") (class "Default")
      (node (ref "U2") (pin "55") (pinfunction "GPIO46_55") (pintype "passive+no_connect"))
    )
    (net (code "61") (name "unconnected-(U2-MTCK-Pad43)") (class "Default")
      (node (ref "U2") (pin "43") (pinfunction "MTCK_43") (pintype "passive+no_connect"))
    )
    (net (code "62") (name "unconnected-(U2-MTDI-Pad46)") (class "Default")
      (node (ref "U2") (pin "46") (pinfunction "MTDI_46") (pintype "passive+no_connect"))
    )
    (net (code "63") (name "unconnected-(U2-MTDO-Pad44)") (class "Default")
      (node (ref "U2") (pin "44") (pinfunction "MTDO_44") (pintype "passive+no_connect"))
    )
    (net (code "64") (name "unconnected-(U2-MTMS-Pad47)") (class "Default")
      (node (ref "U2") (pin "47") (pinfunction "MTMS_47") (pintype "passive+no_connect"))
    )
    (net (code "65") (name "unconnected-(U2-SPICLK-Pad34)") (class "Default")
      (node (ref "U2") (pin "34") (pinfunction "SPICLK_34") (pintype "passive+no_connect"))
    )
    (net (code "66") (name "unconnected-(U2-SPICS0-Pad33)") (class "Default")
      (node (ref "U2") (pin "33") (pinfunction "SPICS0_33") (pintype "passive+no_connect"))
    )
    (net (code "67") (name "unconnected-(U2-SPICS1-Pad29)") (class "Default")
      (node (ref "U2") (pin "29") (pinfunction "SPICS1_29") (pintype "passive+no_connect"))
    )
    (net (code "68") (name "unconnected-(U2-SPID-Pad36)") (class "Default")
      (node (ref "U2") (pin "36") (pinfunction "SPID_36") (pintype "passive+no_connect"))
    )
    (net (code "69") (name "unconnected-(U2-SPIHD-Pad31)") (class "Default")
      (node (ref "U2") (pin "31") (pinfunction "SPIHD_31") (pintype "passive+no_connect"))
    )
    (net (code "70") (name "unconnected-(U2-SPIQ-Pad35)") (class "Default")
      (node (ref "U2") (pin "35") (pinfunction "SPIQ_35") (pintype "passive+no_connect"))
    )
    (net (code "71") (name "unconnected-(U2-SPIWP-Pad32)") (class "Default")
      (node (ref "U2") (pin "32") (pinfunction "SPIWP_32") (pintype "passive+no_connect"))
    )
    (net (code "72") (name "unconnected-(U3-SQW{slash}OUT-Pad7)") (class "Default")
      (node (ref "U3") (pin "7") (pinfunction "SQW/OUT_7") (pintype "passive+no_connect"))
    )
  )
)
